# Carte_Alim_TRACO.net
KiCad netlist of a schematic drawn in Altium Designer
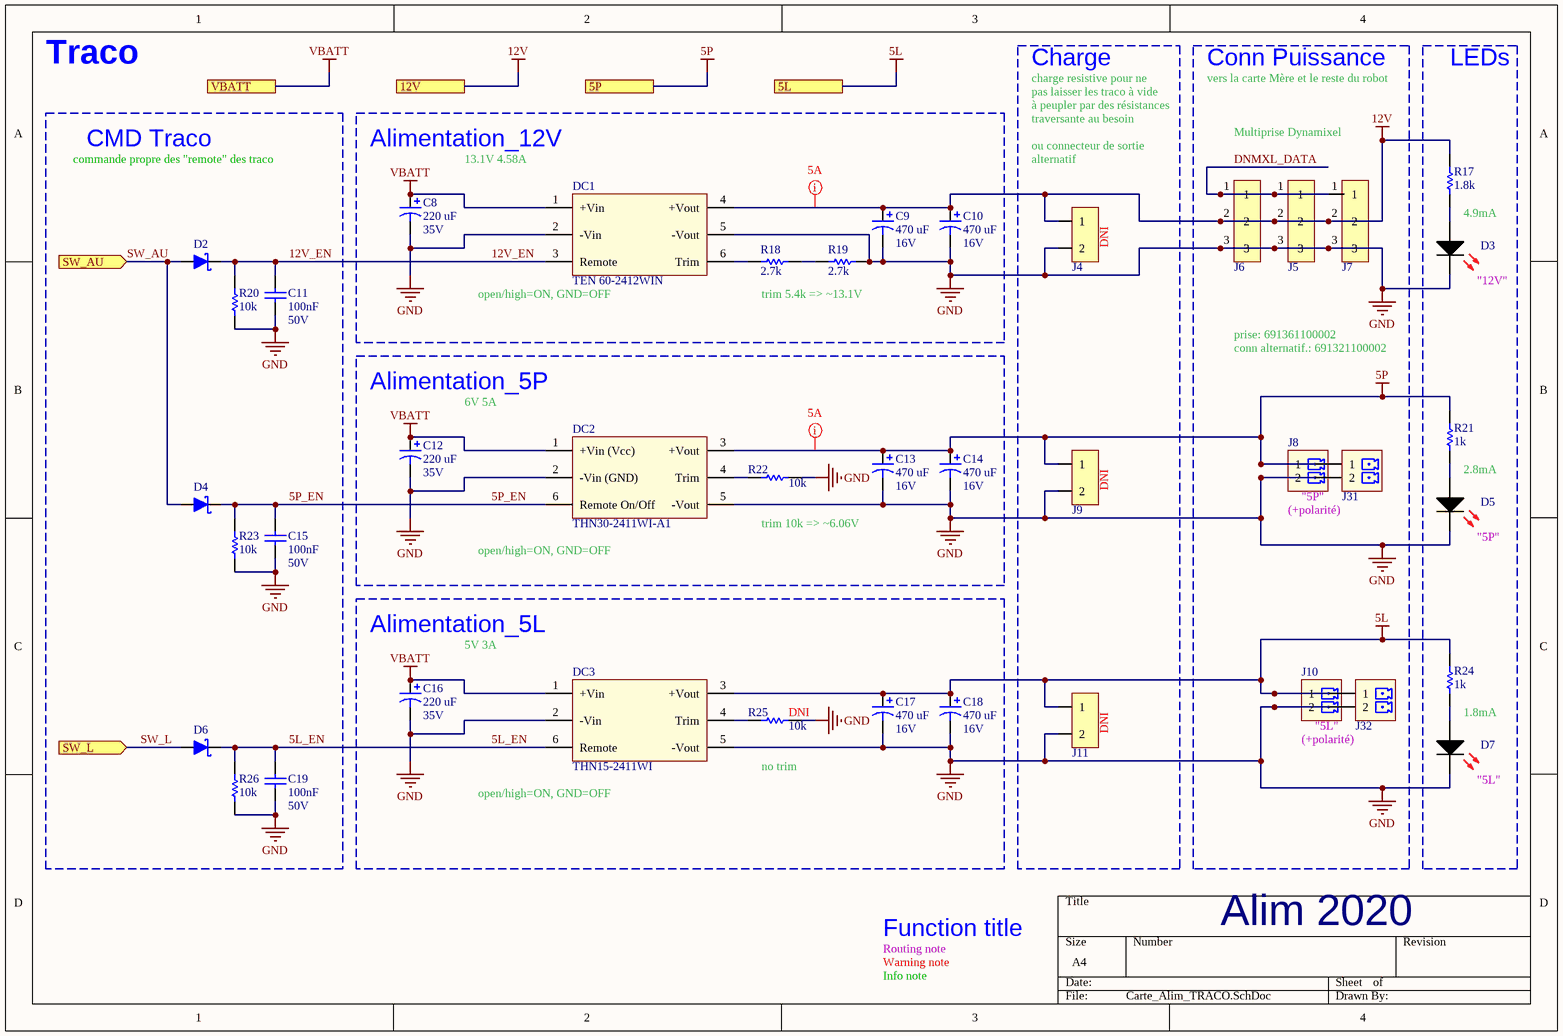
[diagram p0: Carte_Alim_TRACO.SchDoc]

(export (version "E")
  (design (tool "Eeschema 10.0.6"))
  (components
    (comp (ref "C8")
      (value "220 uF")
      (footprint "WCAP-ATG8_8x11.5x3.5x0.5")
      (description "CAP Alu 220 UF 20% 35 V")
      (fields
        (field (name "MANUFACTURER") "Wurth Elektronik")
        (field (name "MANUFACTURER PART NUMBER") "860010574011")
        (field (name "RATEDVOLTAGE") "35V")
      )
      (libsource (lib "Condensateur") (part "WCAP-ATG8, 860010574011"))
    )
    (comp (ref "C9")
      (value "470 uF")
      (footprint "WCAP-ATG8_8x11.5x3.5x0.5")
      (description "CAP Alu 470 UF 20% 16 V")
      (fields
        (field (name "MANUFACTURER") "Wurth Elektronik")
        (field (name "MANUFACTURER PART NUMBER") "860010374012")
        (field (name "RATEDVOLTAGE") "16V")
      )
      (libsource (lib "Condensateur") (part "WCAP-ATG8, 860010374012"))
    )
    (comp (ref "C10")
      (value "470 uF")
      (footprint "WCAP-ATG8_8x11.5x3.5x0.5")
      (description "CAP Alu 470 UF 20% 16 V")
      (fields
        (field (name "MANUFACTURER") "Wurth Elektronik")
        (field (name "MANUFACTURER PART NUMBER") "860010374012")
        (field (name "RATEDVOLTAGE") "16V")
      )
      (libsource (lib "Condensateur") (part "WCAP-ATG8, 860010374012"))
    )
    (comp (ref "C11")
      (value "100nF")
      (footprint "WCAP-CSGP_0603, 1.6x0.8x0.8")
      (description "CAP CER 100nF 50V X7R 0603")
      (fields
        (field (name "RATEDVOLTAGE") "50V")
        (field (name "MANUFACTURER") "Wurth Elektronik")
        (field (name "MANUFACTURER PART NUMBER") "885012206095")
      )
      (libsource (lib "Condensateur") (part "WCAP-CSGP, 885012206095"))
    )
    (comp (ref "C12")
      (value "220 uF")
      (footprint "WCAP-ATG8_8x11.5x3.5x0.5")
      (description "CAP Alu 220 UF 20% 35 V")
      (fields
        (field (name "MANUFACTURER") "Wurth Elektronik")
        (field (name "MANUFACTURER PART NUMBER") "860010574011")
        (field (name "RATEDVOLTAGE") "35V")
      )
      (libsource (lib "Condensateur") (part "WCAP-ATG8, 860010574011"))
    )
    (comp (ref "C13")
      (value "470 uF")
      (footprint "WCAP-ATG8_8x11.5x3.5x0.5")
      (description "CAP Alu 470 UF 20% 16 V")
      (fields
        (field (name "MANUFACTURER") "Wurth Elektronik")
        (field (name "MANUFACTURER PART NUMBER") "860010374012")
        (field (name "RATEDVOLTAGE") "16V")
      )
      (libsource (lib "Condensateur") (part "WCAP-ATG8, 860010374012"))
    )
    (comp (ref "C14")
      (value "470 uF")
      (footprint "WCAP-ATG8_8x11.5x3.5x0.5")
      (description "CAP Alu 470 UF 20% 16 V")
      (fields
        (field (name "MANUFACTURER") "Wurth Elektronik")
        (field (name "MANUFACTURER PART NUMBER") "860010374012")
        (field (name "RATEDVOLTAGE") "16V")
      )
      (libsource (lib "Condensateur") (part "WCAP-ATG8, 860010374012"))
    )
    (comp (ref "C15")
      (value "100nF")
      (footprint "WCAP-CSGP_0603, 1.6x0.8x0.8")
      (description "CAP CER 100nF 50V X7R 0603")
      (fields
        (field (name "RATEDVOLTAGE") "50V")
        (field (name "MANUFACTURER") "Wurth Elektronik")
        (field (name "MANUFACTURER PART NUMBER") "885012206095")
      )
      (libsource (lib "Condensateur") (part "WCAP-CSGP, 885012206095"))
    )
    (comp (ref "C16")
      (value "220 uF")
      (footprint "WCAP-ATG8_8x11.5x3.5x0.5")
      (description "CAP Alu 220 UF 20% 35 V")
      (fields
        (field (name "MANUFACTURER") "Wurth Elektronik")
        (field (name "MANUFACTURER PART NUMBER") "860010574011")
        (field (name "RATEDVOLTAGE") "35V")
      )
      (libsource (lib "Condensateur") (part "WCAP-ATG8, 860010574011"))
    )
    (comp (ref "C17")
      (value "470 uF")
      (footprint "WCAP-ATG8_8x11.5x3.5x0.5")
      (description "CAP Alu 470 UF 20% 16 V")
      (fields
        (field (name "MANUFACTURER") "Wurth Elektronik")
        (field (name "MANUFACTURER PART NUMBER") "860010374012")
        (field (name "RATEDVOLTAGE") "16V")
      )
      (libsource (lib "Condensateur") (part "WCAP-ATG8, 860010374012"))
    )
    (comp (ref "C18")
      (value "470 uF")
      (footprint "WCAP-ATG8_8x11.5x3.5x0.5")
      (description "CAP Alu 470 UF 20% 16 V")
      (fields
        (field (name "MANUFACTURER") "Wurth Elektronik")
        (field (name "MANUFACTURER PART NUMBER") "860010374012")
        (field (name "RATEDVOLTAGE") "16V")
      )
      (libsource (lib "Condensateur") (part "WCAP-ATG8, 860010374012"))
    )
    (comp (ref "C19")
      (value "100nF")
      (footprint "WCAP-CSGP_0603, 1.6x0.8x0.8")
      (description "CAP CER 100nF 50V X7R 0603")
      (fields
        (field (name "RATEDVOLTAGE") "50V")
        (field (name "MANUFACTURER") "Wurth Elektronik")
        (field (name "MANUFACTURER PART NUMBER") "885012206095")
      )
      (libsource (lib "Condensateur") (part "WCAP-CSGP, 885012206095"))
    )
    (comp (ref "D2")
      (value "RBR3MM40ATFTR")
      (footprint "SOD-123FL")
      (description "DIODE SCHOTTKY 40V 3A SOD123-FL")
      (fields (field (name "MANUFACTURER") "ROHM"))
      (libsource (lib "Diode") (part "RBR3MM40ATFTR"))
    )
    (comp (ref "D3")
      (value "150060RS75000")
      (footprint "SMCW_0603")
      (description "SMD mono-color Chip LED, WL-SMCW, Red")
      (fields (field (name "MANUFACTURER") "Wurth Elektronik"))
      (libsource (lib "Opto") (part "WL-SMCW 0603  150060RS75000"))
    )
    (comp (ref "D4")
      (value "RBR3MM40ATFTR")
      (footprint "SOD-123FL")
      (description "DIODE SCHOTTKY 40V 3A SOD123-FL")
      (fields (field (name "MANUFACTURER") "ROHM"))
      (libsource (lib "Diode") (part "RBR3MM40ATFTR"))
    )
    (comp (ref "D5")
      (value "150060RS75000")
      (footprint "SMCW_0603")
      (description "SMD mono-color Chip LED, WL-SMCW, Red")
      (fields (field (name "MANUFACTURER") "Wurth Elektronik"))
      (libsource (lib "Opto") (part "WL-SMCW 0603  150060RS75000"))
    )
    (comp (ref "D6")
      (value "RBR3MM40ATFTR")
      (footprint "SOD-123FL")
      (description "DIODE SCHOTTKY 40V 3A SOD123-FL")
      (fields (field (name "MANUFACTURER") "ROHM"))
      (libsource (lib "Diode") (part "RBR3MM40ATFTR"))
    )
    (comp (ref "D7")
      (value "150060RS75000")
      (footprint "SMCW_0603")
      (description "SMD mono-color Chip LED, WL-SMCW, Red")
      (fields (field (name "MANUFACTURER") "Wurth Elektronik"))
      (libsource (lib "Opto") (part "WL-SMCW 0603  150060RS75000"))
    )
    (comp (ref "DC1")
      (value "TEN 60-2412WIN")
      (footprint "TEN 60")
      (description "Traco 12.0V 60W 5A")
      (fields (field (name "MANUFACTURER") "TRACOPOWER"))
      (libsource (lib "Alimentation") (part "TEN 60-2412WIN"))
    )
    (comp (ref "DC2")
      (value "THN30-2411WI-A1")
      (footprint "THN 30WI-A1")
      (description "Traco 5V-6V 30W 6A")
      (fields (field (name "MANUFACTURER") "TRACOPOWER"))
      (libsource (lib "Alimentation") (part "THN30-2411WI-A1"))
    )
    (comp (ref "DC3")
      (value "THN15-2411WI")
      (footprint "THN 15WI")
      (description "Traco 5V 15W 3A")
      (fields (field (name "MANUFACTURER") "TRACOPOWER"))
      (libsource (lib "Alimentation") (part "THN15-2411WI"))
    )
    (comp (ref "J4")
      (value "22-03-2021")
      (footprint "22-03-2021")
      (description "CONN HEADER VERT 2POS 2.54MM")
      (fields (field (name "MANUFACTURER") "MOLEX"))
      (libsource (lib "Connecteurs") (part "22-03-2021"))
    )
    (comp (ref "J5")
      (value "22-03-5035")
      (footprint "20-03-5035")
      (description "CONN HEADER VERT 3POS 2.5MM")
      (fields (field (name "MANUFACTURER") "MOLEX"))
      (libsource (lib "Connecteurs") (part "20-03-5035"))
    )
    (comp (ref "J6")
      (value "22-03-5035")
      (footprint "20-03-5035")
      (description "CONN HEADER VERT 3POS 2.5MM")
      (fields (field (name "MANUFACTURER") "MOLEX"))
      (libsource (lib "Connecteurs") (part "20-03-5035"))
    )
    (comp (ref "J7")
      (value "22-03-5035")
      (footprint "20-03-5035")
      (description "CONN HEADER VERT 3POS 2.5MM")
      (fields (field (name "MANUFACTURER") "MOLEX"))
      (libsource (lib "Connecteurs") (part "20-03-5035"))
    )
    (comp (ref "J8")
      (value "691322110002")
      (footprint "691322110002")
      (description "WR-TBL 2p Series 3221 - 3.50 mm Horizontal PCB Header")
      (fields (field (name "MANUFACTURER") "Wurth Electronics Inc."))
      (libsource (lib "Connecteurs") (part "691322110002"))
    )
    (comp (ref "J9")
      (value "22-03-2021")
      (footprint "22-03-2021")
      (description "CONN HEADER VERT 2POS 2.54MM")
      (fields (field (name "MANUFACTURER") "MOLEX"))
      (libsource (lib "Connecteurs") (part "22-03-2021"))
    )
    (comp (ref "J10")
      (value "691322110002")
      (footprint "691322110002")
      (description "WR-TBL 2p Series 3221 - 3.50 mm Horizontal PCB Header")
      (fields (field (name "MANUFACTURER") "Wurth Electronics Inc."))
      (libsource (lib "Connecteurs") (part "691322110002"))
    )
    (comp (ref "J11")
      (value "22-03-2021")
      (footprint "22-03-2021")
      (description "CONN HEADER VERT 2POS 2.54MM")
      (fields (field (name "MANUFACTURER") "MOLEX"))
      (libsource (lib "Connecteurs") (part "22-03-2021"))
    )
    (comp (ref "J31")
      (value "691321100002")
      (footprint "691321100002")
      (description "WR-TBL 2p Series 3211 - 3.50 mm Vertical PCB Header")
      (fields (field (name "MANUFACTURER") "Wurth Electronics Inc."))
      (libsource (lib "Connecteurs") (part "691321100002"))
    )
    (comp (ref "J32")
      (value "691321100002")
      (footprint "691321100002")
      (description "WR-TBL 2p Series 3211 - 3.50 mm Vertical PCB Header")
      (fields (field (name "MANUFACTURER") "Wurth Electronics Inc."))
      (libsource (lib "Connecteurs") (part "691321100002"))
    )
    (comp (ref "R17")
      (value "1.8k")
      (footprint "RESC1608X06N")
      (description "RES SMD 1.8K OHM 1% 1/10W 0603")
      (fields
        (field (name "MANUFACTURER") "Yageo")
        (field (name "MANUFACTURER PART NUMBER") "RC0603FR-071K8L")
      )
      (libsource (lib "Resistance") (part "RC0603FR-071K8L"))
    )
    (comp (ref "R18")
      (value "2.7k")
      (footprint "RESC2012X06N")
      (description "RES SMD 2K7 OHM 1% 1/8W 0805")
      (fields
        (field (name "MANUFACTURER") "Yageo")
        (field (name "MANUFACTURER PART NUMBER") "RC0805FR-072K7L")
      )
      (libsource (lib "Resistance") (part "RC0805FR-072K7L"))
    )
    (comp (ref "R19")
      (value "2.7k")
      (footprint "RESC2012X06N")
      (description "RES SMD 2K7 OHM 1% 1/8W 0805")
      (fields
        (field (name "MANUFACTURER") "Yageo")
        (field (name "MANUFACTURER PART NUMBER") "RC0805FR-072K7L")
      )
      (libsource (lib "Resistance") (part "RC0805FR-072K7L"))
    )
    (comp (ref "R20")
      (value "10k")
      (footprint "RESC1608X06N")
      (description "RES SMD 10K OHM 1% 1/10W 0603")
      (fields
        (field (name "MANUFACTURER") "Yageo")
        (field (name "MANUFACTURER PART NUMBER") "RC0603FR-0710KL")
      )
      (libsource (lib "Resistance") (part "RC0603FR-0710KL"))
    )
    (comp (ref "R21")
      (value "1k")
      (footprint "RESC1608X06N")
      (description "RES SMD 1K OHM 1% 1/10W 0603")
      (fields
        (field (name "MANUFACTURER") "Yageo")
        (field (name "MANUFACTURER PART NUMBER") "RC0603FR-071KL")
      )
      (libsource (lib "Resistance") (part "RC0603FR-071KL"))
    )
    (comp (ref "R22")
      (value "10k")
      (footprint "RESC1608X06N")
      (description "RES SMD 10K OHM 1% 1/10W 0603")
      (fields
        (field (name "MANUFACTURER") "Yageo")
        (field (name "MANUFACTURER PART NUMBER") "RC0603FR-0710KL")
      )
      (libsource (lib "Resistance") (part "RC0603FR-0710KL"))
    )
    (comp (ref "R23")
      (value "10k")
      (footprint "RESC1608X06N")
      (description "RES SMD 10K OHM 1% 1/10W 0603")
      (fields
        (field (name "MANUFACTURER") "Yageo")
        (field (name "MANUFACTURER PART NUMBER") "RC0603FR-0710KL")
      )
      (libsource (lib "Resistance") (part "RC0603FR-0710KL"))
    )
    (comp (ref "R24")
      (value "1k")
      (footprint "RESC1608X06N")
      (description "RES SMD 1K OHM 1% 1/10W 0603")
      (fields
        (field (name "MANUFACTURER") "Yageo")
        (field (name "MANUFACTURER PART NUMBER") "RC0603FR-071KL")
      )
      (libsource (lib "Resistance") (part "RC0603FR-071KL"))
    )
    (comp (ref "R25")
      (value "10k")
      (footprint "RESC1608X06N")
      (description "RES SMD 10K OHM 1% 1/10W 0603")
      (fields
        (field (name "MANUFACTURER") "Yageo")
        (field (name "MANUFACTURER PART NUMBER") "RC0603FR-0710KL")
      )
      (libsource (lib "Resistance") (part "RC0603FR-0710KL"))
    )
    (comp (ref "R26")
      (value "10k")
      (footprint "RESC1608X06N")
      (description "RES SMD 10K OHM 1% 1/10W 0603")
      (fields
        (field (name "MANUFACTURER") "Yageo")
        (field (name "MANUFACTURER PART NUMBER") "RC0603FR-0710KL")
      )
      (libsource (lib "Resistance") (part "RC0603FR-0710KL"))
    )
  )
  (nets
    (net (code "1") (name "/5L_EN") (class "Default")
      (node (ref "C19") (pin "2") (pinfunction "2_2") (pintype "passive"))
      (node (ref "D6") (pin "2") (pintype "passive"))
      (node (ref "DC3") (pin "6") (pinfunction "Remote_6") (pintype "power_in"))
      (node (ref "R26") (pin "2") (pinfunction "2_2") (pintype "passive"))
    )
    (net (code "2") (name "/5P_EN") (class "Default")
      (node (ref "C15") (pin "2") (pinfunction "2_2") (pintype "passive"))
      (node (ref "D4") (pin "2") (pintype "passive"))
      (node (ref "DC2") (pin "6") (pinfunction "Remote_On/Off_6") (pintype "power_in"))
      (node (ref "R23") (pin "2") (pinfunction "2_2") (pintype "passive"))
    )
    (net (code "3") (name "/12V_EN") (class "Default")
      (node (ref "C11") (pin "2") (pinfunction "2_2") (pintype "passive"))
      (node (ref "D2") (pin "2") (pintype "passive"))
      (node (ref "DC1") (pin "3") (pinfunction "Remote_3") (pintype "power_in"))
      (node (ref "R20") (pin "2") (pinfunction "2_2") (pintype "passive"))
    )
    (net (code "4") (name "/DNMXL_DATA") (class "Default")
      (node (ref "J5") (pin "1") (pinfunction "1_1") (pintype "passive"))
      (node (ref "J6") (pin "1") (pinfunction "1_1") (pintype "passive"))
      (node (ref "J7") (pin "1") (pinfunction "1_1") (pintype "passive"))
    )
    (net (code "5") (name "/SW_AU") (class "Default")
      (node (ref "D2") (pin "1") (pintype "passive"))
      (node (ref "D4") (pin "1") (pintype "passive"))
    )
    (net (code "6") (name "/SW_L") (class "Default") (node (ref "D6") (pin "1") (pintype "passive")))
    (net (code "7") (name "5L") (class "Default")
      (node (ref "C17") (pin "1") (pinfunction "1_1") (pintype "passive"))
      (node (ref "C18") (pin "1") (pinfunction "1_1") (pintype "passive"))
      (node (ref "DC3") (pin "3") (pinfunction "+Vout_3") (pintype "power_in"))
      (node (ref "J10") (pin "1") (pinfunction "1_1") (pintype "passive"))
      (node (ref "J11") (pin "1") (pinfunction "1_1") (pintype "passive"))
      (node (ref "J32") (pin "1") (pinfunction "1_1") (pintype "passive"))
      (node (ref "R24") (pin "1") (pinfunction "1_1") (pintype "passive"))
    )
    (net (code "8") (name "5P") (class "Default")
      (node (ref "C13") (pin "1") (pinfunction "1_1") (pintype "passive"))
      (node (ref "C14") (pin "1") (pinfunction "1_1") (pintype "passive"))
      (node (ref "DC2") (pin "3") (pinfunction "+Vout_3") (pintype "power_in"))
      (node (ref "J31") (pin "1") (pinfunction "1_1") (pintype "passive"))
      (node (ref "J8") (pin "1") (pinfunction "1_1") (pintype "passive"))
      (node (ref "J9") (pin "1") (pinfunction "1_1") (pintype "passive"))
      (node (ref "R21") (pin "1") (pinfunction "1_1") (pintype "passive"))
    )
    (net (code "9") (name "12V") (class "Default")
      (node (ref "C10") (pin "1") (pinfunction "1_1") (pintype "passive"))
      (node (ref "C9") (pin "1") (pinfunction "1_1") (pintype "passive"))
      (node (ref "DC1") (pin "4") (pinfunction "+Vout_4") (pintype "power_in"))
      (node (ref "J4") (pin "1") (pinfunction "1_1") (pintype "passive"))
      (node (ref "J5") (pin "2") (pinfunction "2_2") (pintype "passive"))
      (node (ref "J6") (pin "2") (pinfunction "2_2") (pintype "passive"))
      (node (ref "J7") (pin "2") (pinfunction "2_2") (pintype "passive"))
      (node (ref "R17") (pin "2") (pinfunction "2_2") (pintype "passive"))
    )
    (net (code "10") (name "GND") (class "Default")
      (node (ref "C10") (pin "2") (pinfunction "2_2") (pintype "passive"))
      (node (ref "C11") (pin "1") (pinfunction "1_1") (pintype "passive"))
      (node (ref "C12") (pin "2") (pinfunction "2_2") (pintype "passive"))
      (node (ref "C13") (pin "2") (pinfunction "2_2") (pintype "passive"))
      (node (ref "C14") (pin "2") (pinfunction "2_2") (pintype "passive"))
      (node (ref "C15") (pin "1") (pinfunction "1_1") (pintype "passive"))
      (node (ref "C16") (pin "2") (pinfunction "2_2") (pintype "passive"))
      (node (ref "C17") (pin "2") (pinfunction "2_2") (pintype "passive"))
      (node (ref "C18") (pin "2") (pinfunction "2_2") (pintype "passive"))
      (node (ref "C19") (pin "1") (pinfunction "1_1") (pintype "passive"))
      (node (ref "C8") (pin "2") (pinfunction "2_2") (pintype "passive"))
      (node (ref "C9") (pin "2") (pinfunction "2_2") (pintype "passive"))
      (node (ref "D3") (pin "1") (pinfunction "C_1") (pintype "passive"))
      (node (ref "D5") (pin "1") (pinfunction "C_1") (pintype "passive"))
      (node (ref "D7") (pin "1") (pinfunction "C_1") (pintype "passive"))
      (node (ref "DC1") (pin "2") (pinfunction "-Vin_2") (pintype "power_in"))
      (node (ref "DC1") (pin "5") (pinfunction "-Vout_5") (pintype "power_in"))
      (node (ref "DC2") (pin "2") (pinfunction "-Vin_(GND)_2") (pintype "power_in"))
      (node (ref "DC2") (pin "5") (pinfunction "-Vout_5") (pintype "power_in"))
      (node (ref "DC3") (pin "2") (pinfunction "-Vin_2") (pintype "power_in"))
      (node (ref "DC3") (pin "5") (pinfunction "-Vout_5") (pintype "power_in"))
      (node (ref "J10") (pin "2") (pinfunction "2_2") (pintype "passive"))
      (node (ref "J11") (pin "2") (pinfunction "2_2") (pintype "passive"))
      (node (ref "J31") (pin "2") (pinfunction "2_2") (pintype "passive"))
      (node (ref "J32") (pin "2") (pinfunction "2_2") (pintype "passive"))
      (node (ref "J4") (pin "2") (pinfunction "2_2") (pintype "passive"))
      (node (ref "J5") (pin "3") (pinfunction "3_3") (pintype "passive"))
      (node (ref "J6") (pin "3") (pinfunction "3_3") (pintype "passive"))
      (node (ref "J7") (pin "3") (pinfunction "3_3") (pintype "passive"))
      (node (ref "J8") (pin "2") (pinfunction "2_2") (pintype "passive"))
      (node (ref "J9") (pin "2") (pinfunction "2_2") (pintype "passive"))
      (node (ref "R19") (pin "2") (pinfunction "2_2") (pintype "passive"))
      (node (ref "R20") (pin "1") (pinfunction "1_1") (pintype "passive"))
      (node (ref "R22") (pin "2") (pinfunction "2_2") (pintype "passive"))
      (node (ref "R23") (pin "1") (pinfunction "1_1") (pintype "passive"))
      (node (ref "R25") (pin "2") (pinfunction "2_2") (pintype "passive"))
      (node (ref "R26") (pin "1") (pinfunction "1_1") (pintype "passive"))
    )
    (net (code "11") (name "Net-(D3-A)") (class "Default")
      (node (ref "D3") (pin "2") (pinfunction "A_2") (pintype "passive"))
      (node (ref "R17") (pin "1") (pinfunction "1_1") (pintype "passive"))
    )
    (net (code "12") (name "Net-(D5-A)") (class "Default")
      (node (ref "D5") (pin "2") (pinfunction "A_2") (pintype "passive"))
      (node (ref "R21") (pin "2") (pinfunction "2_2") (pintype "passive"))
    )
    (net (code "13") (name "Net-(D7-A)") (class "Default")
      (node (ref "D7") (pin "2") (pinfunction "A_2") (pintype "passive"))
      (node (ref "R24") (pin "2") (pinfunction "2_2") (pintype "passive"))
    )
    (net (code "14") (name "Net-(DC1-Trim)") (class "Default")
      (node (ref "DC1") (pin "6") (pinfunction "Trim_6") (pintype "power_in"))
      (node (ref "R18") (pin "1") (pinfunction "1_1") (pintype "passive"))
    )
    (net (code "15") (name "Net-(DC2-Trim)") (class "Default")
      (node (ref "DC2") (pin "4") (pinfunction "Trim_4") (pintype "power_in"))
      (node (ref "R22") (pin "1") (pinfunction "1_1") (pintype "passive"))
    )
    (net (code "16") (name "Net-(DC3-Trim)") (class "Default")
      (node (ref "DC3") (pin "4") (pinfunction "Trim_4") (pintype "power_in"))
      (node (ref "R25") (pin "1") (pinfunction "1_1") (pintype "passive"))
    )
    (net (code "17") (name "Net-(R18-Pad2)") (class "Default")
      (node (ref "R18") (pin "2") (pinfunction "2_2") (pintype "passive"))
      (node (ref "R19") (pin "1") (pinfunction "1_1") (pintype "passive"))
    )
    (net (code "18") (name "VBATT") (class "Default")
      (node (ref "C12") (pin "1") (pinfunction "1_1") (pintype "passive"))
      (node (ref "C16") (pin "1") (pinfunction "1_1") (pintype "passive"))
      (node (ref "C8") (pin "1") (pinfunction "1_1") (pintype "passive"))
      (node (ref "DC1") (pin "1") (pinfunction "+Vin_1") (pintype "power_in"))
      (node (ref "DC2") (pin "1") (pinfunction "+Vin_(Vcc)_1") (pintype "power_in"))
      (node (ref "DC3") (pin "1") (pinfunction "+Vin_1") (pintype "power_in"))
    )
  )
)
